# 00A-005_Fuse_Post_Board.net
KiCad netlist of a schematic drawn in EAGLE
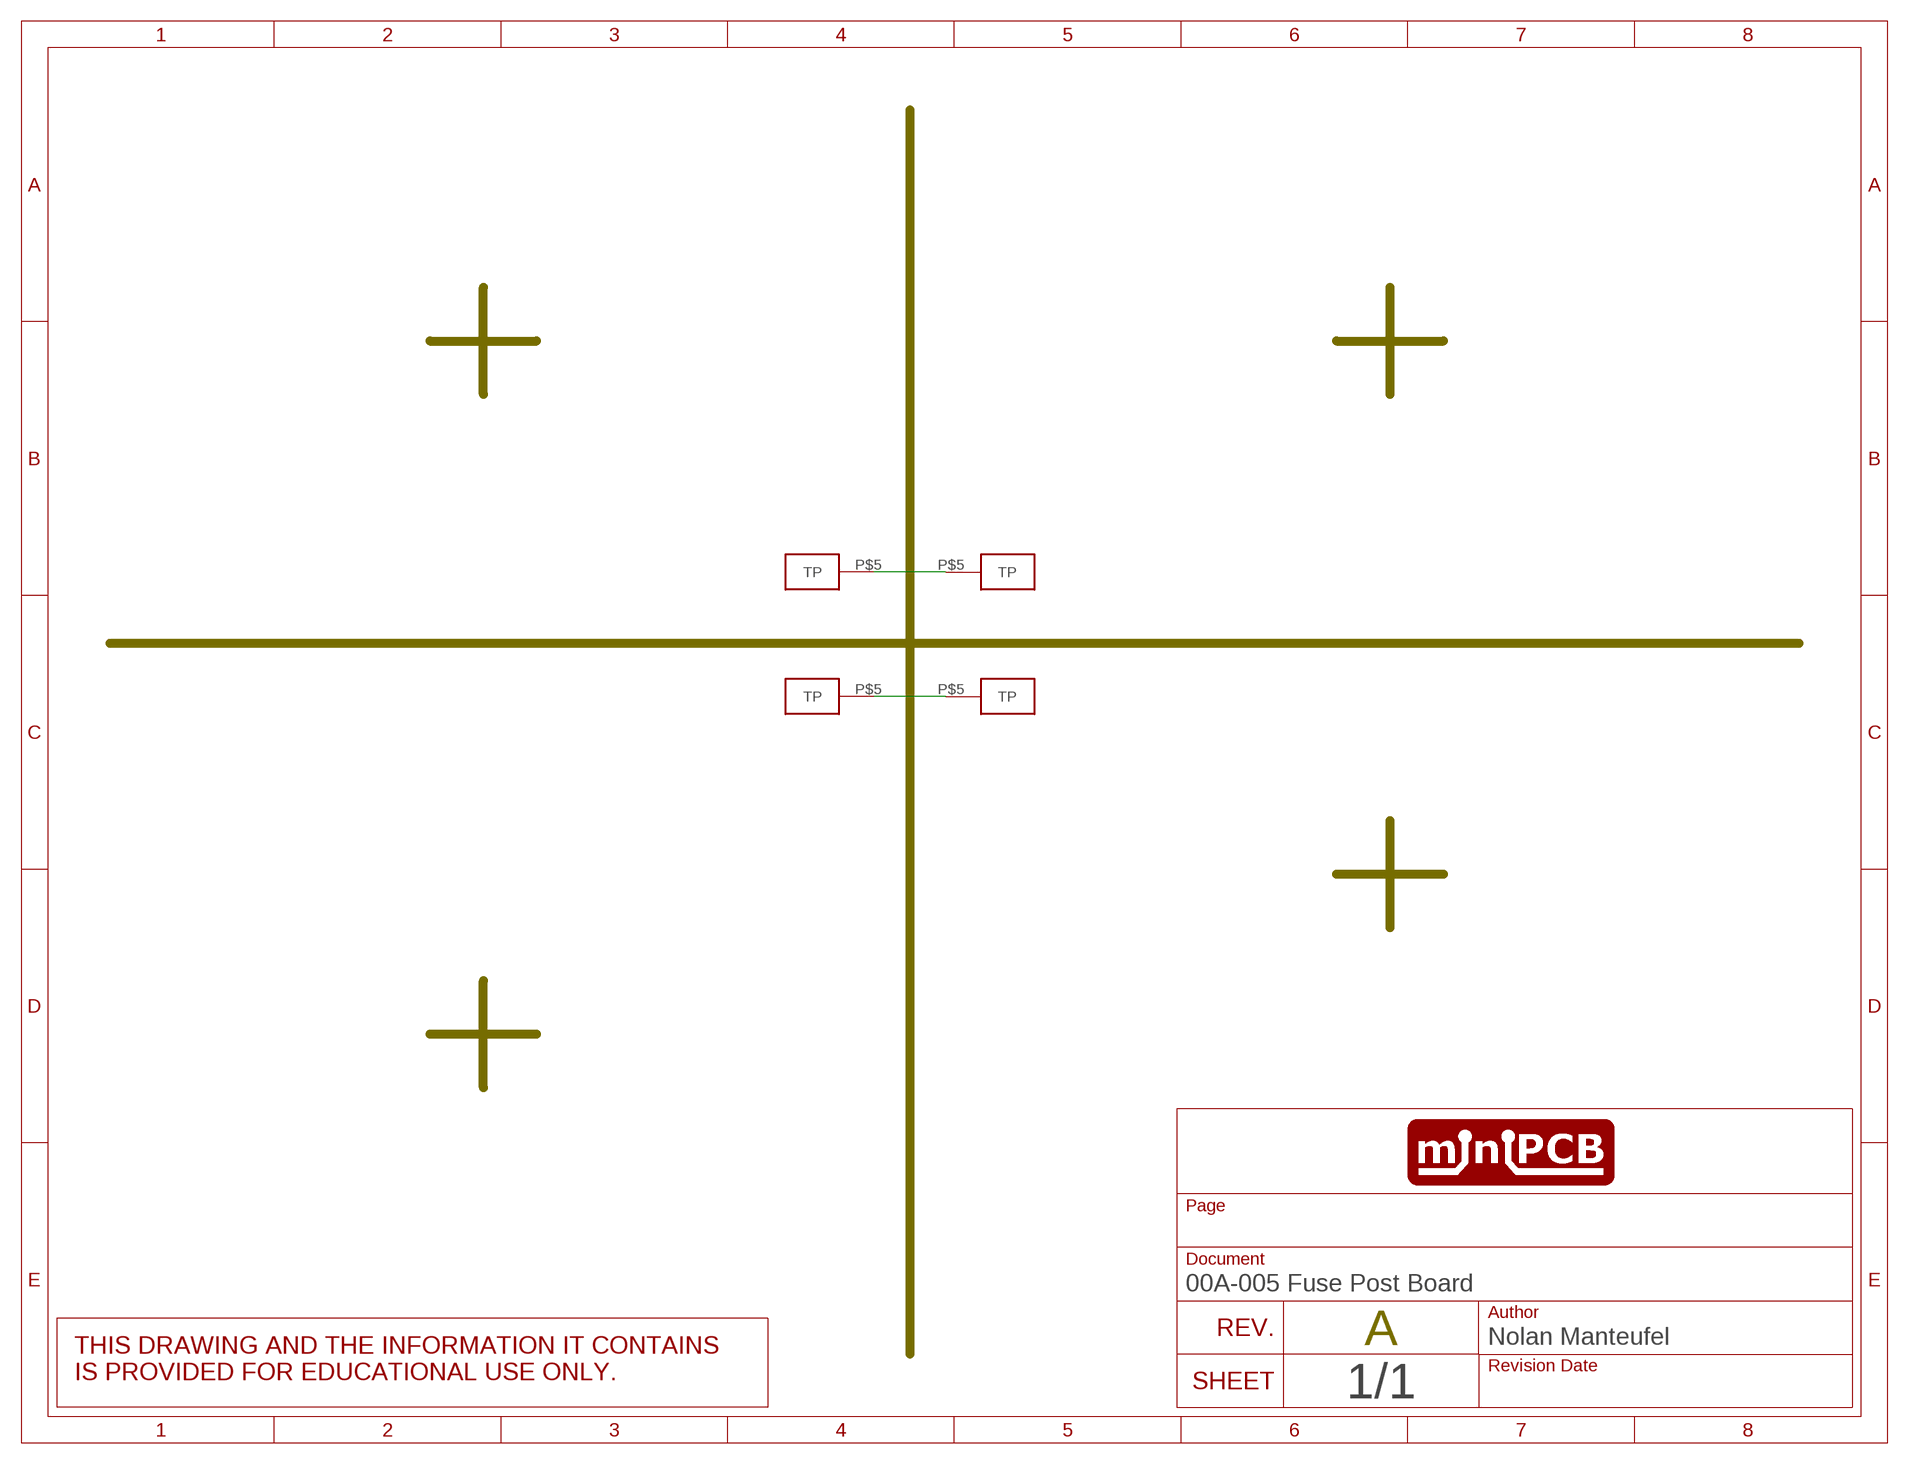
[diagram p0: schematic, sheet 1]

(export (version "E")
  (design (tool "Eeschema 10.0.6"))
  (components
    (comp (ref "U$1")
      (value "TESTPOINT2M4")
      (footprint "eagle-import:SCREW_TERMINAL_M4")
      (libsource (lib "eagle-import") (part "TESTPOINT2M4"))
    )
    (comp (ref "U$2")
      (value "TESTPOINT2M4")
      (footprint "eagle-import:SCREW_TERMINAL_M4")
      (libsource (lib "eagle-import") (part "TESTPOINT2M4"))
    )
    (comp (ref "U$3")
      (value "TESTPOINT2M4")
      (footprint "eagle-import:SCREW_TERMINAL_M4")
      (libsource (lib "eagle-import") (part "TESTPOINT2M4"))
    )
    (comp (ref "U$4")
      (value "TESTPOINT2M4")
      (footprint "eagle-import:SCREW_TERMINAL_M4")
      (libsource (lib "eagle-import") (part "TESTPOINT2M4"))
    )
  )
  (nets
    (net (code "1") (name "Net-(U$1-TP)") (class "Default")
      (node (ref "U$1") (pin "P$5") (pinfunction "TP_P$5") (pintype "bidirectional"))
      (node (ref "U$3") (pin "P$5") (pinfunction "TP_P$5") (pintype "bidirectional"))
    )
    (net (code "2") (name "Net-(U$2-TP)") (class "Default")
      (node (ref "U$2") (pin "P$5") (pinfunction "TP_P$5") (pintype "bidirectional"))
      (node (ref "U$4") (pin "P$5") (pinfunction "TP_P$5") (pintype "bidirectional"))
    )
  )
)
